# DAC.net
KiCad netlist of a schematic drawn in Altium Designer
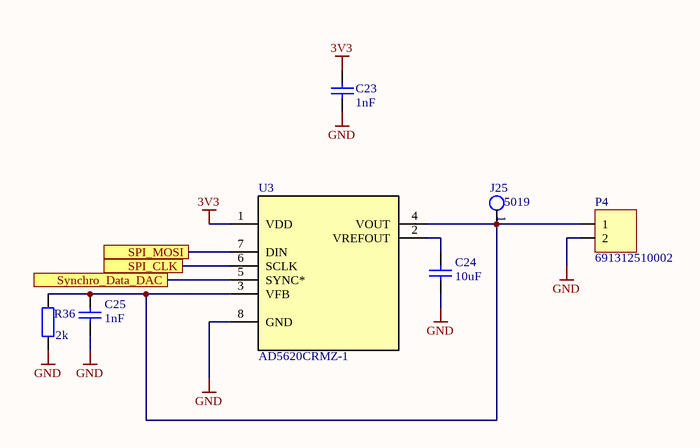
[diagram p0: DAC.SchDoc]

(export (version "E")
  (design (tool "Eeschema 10.0.6"))
  (components
    (comp (ref "C23")
      (value "1nF")
      (footprint "C0805")
      (description "Capacitor")
      (fields (field (name "PUBLISHER") "Altium Limited"))
      (libsource (lib "Miscellaneous Devices") (part "Cap"))
    )
    (comp (ref "C24")
      (value "10uF")
      (footprint "C0805")
      (description "Capacitor")
      (fields (field (name "PUBLISHER") "Altium Limited"))
      (libsource (lib "Miscellaneous Devices") (part "Cap"))
    )
    (comp (ref "C25")
      (value "1nF")
      (footprint "C0805")
      (description "Capacitor")
      (fields (field (name "PUBLISHER") "Altium Limited"))
      (libsource (lib "Miscellaneous Devices") (part "Cap"))
    )
    (comp (ref "J25")
      (value "5019")
      (footprint "KEYSTONE_5019")
      (fields (field (name "MANUFACTURER") "Keystone Electronics"))
      (libsource (lib "2225B_VumetreFrequenciel") (part "CMP-1672-00008-2"))
    )
    (comp (ref "P4")
      (value "691312510002")
      (footprint "LINX_CONBNC002")
      (description "Header, 2-Pin")
      (fields (field (name "PUBLISHER") "Altium Limited"))
      (libsource (lib "2225B_VumetreFrequenciel") (part "MHDR1X2"))
    )
    (comp (ref "R36")
      (value "2k")
      (footprint "RESC2012X06M")
      (description "Resistor")
      (fields (field (name "PUBLISHER") "Altium Limited"))
      (libsource (lib "Miscellaneous Devices") (part "Res2"))
    )
    (comp (ref "U3")
      (value "AD5620CRMZ-1")
      (footprint "SOP65P490X110-8N")
      (description "Single, 12-Bit nanoDACÂ® with 5 ppm/Â°C On-Chip Reference in SOT-23")
      (fields (field (name "MF") "Analog Devices"))
      (libsource (lib "2227_BoiteBruitage") (part "AD5620CRMZ-1"))
    )
  )
  (nets
    (net (code "1") (name "/SPI_CLK") (class "Default")
      (node (ref "U3") (pin "6") (pinfunction "SCLK_6") (pintype "passive"))
    )
    (net (code "2") (name "/SPI_MOSI") (class "Default")
      (node (ref "U3") (pin "7") (pinfunction "DIN_7") (pintype "passive"))
    )
    (net (code "3") (name "/Synchro_Data_DAC") (class "Default")
      (node (ref "U3") (pin "5") (pinfunction "SYNC*_5") (pintype "passive"))
    )
    (net (code "4") (name "3V3") (class "Default")
      (node (ref "C23") (pin "2") (pinfunction "2_2") (pintype "passive"))
      (node (ref "U3") (pin "1") (pinfunction "VDD_1") (pintype "power_in"))
    )
    (net (code "5") (name "GND") (class "Default")
      (node (ref "C23") (pin "1") (pinfunction "1_1") (pintype "passive"))
      (node (ref "C24") (pin "1") (pinfunction "1_1") (pintype "passive"))
      (node (ref "C25") (pin "1") (pinfunction "1_1") (pintype "passive"))
      (node (ref "P4") (pin "2") (pinfunction "2_2") (pintype "passive"))
      (node (ref "R36") (pin "1") (pinfunction "1_1") (pintype "passive"))
      (node (ref "U3") (pin "8") (pinfunction "GND_8") (pintype "passive"))
    )
    (net (code "6") (name "Net-(U3-VFB)") (class "Default")
      (node (ref "C25") (pin "2") (pinfunction "2_2") (pintype "passive"))
      (node (ref "J25") (pin "1") (pinfunction "1_1") (pintype "passive"))
      (node (ref "P4") (pin "1") (pinfunction "1_1") (pintype "passive"))
      (node (ref "R36") (pin "2") (pinfunction "2_2") (pintype "passive"))
      (node (ref "U3") (pin "3") (pinfunction "VFB_3") (pintype "passive"))
      (node (ref "U3") (pin "4") (pinfunction "VOUT_4") (pintype "passive"))
    )
    (net (code "7") (name "Net-(U3-VREFOUT)") (class "Default")
      (node (ref "C24") (pin "2") (pinfunction "2_2") (pintype "passive"))
      (node (ref "U3") (pin "2") (pinfunction "VREFOUT_2") (pintype "passive"))
    )
  )
)
